# stm32LoRaAccel.net
KiCad netlist of a schematic drawn in Altium Designer
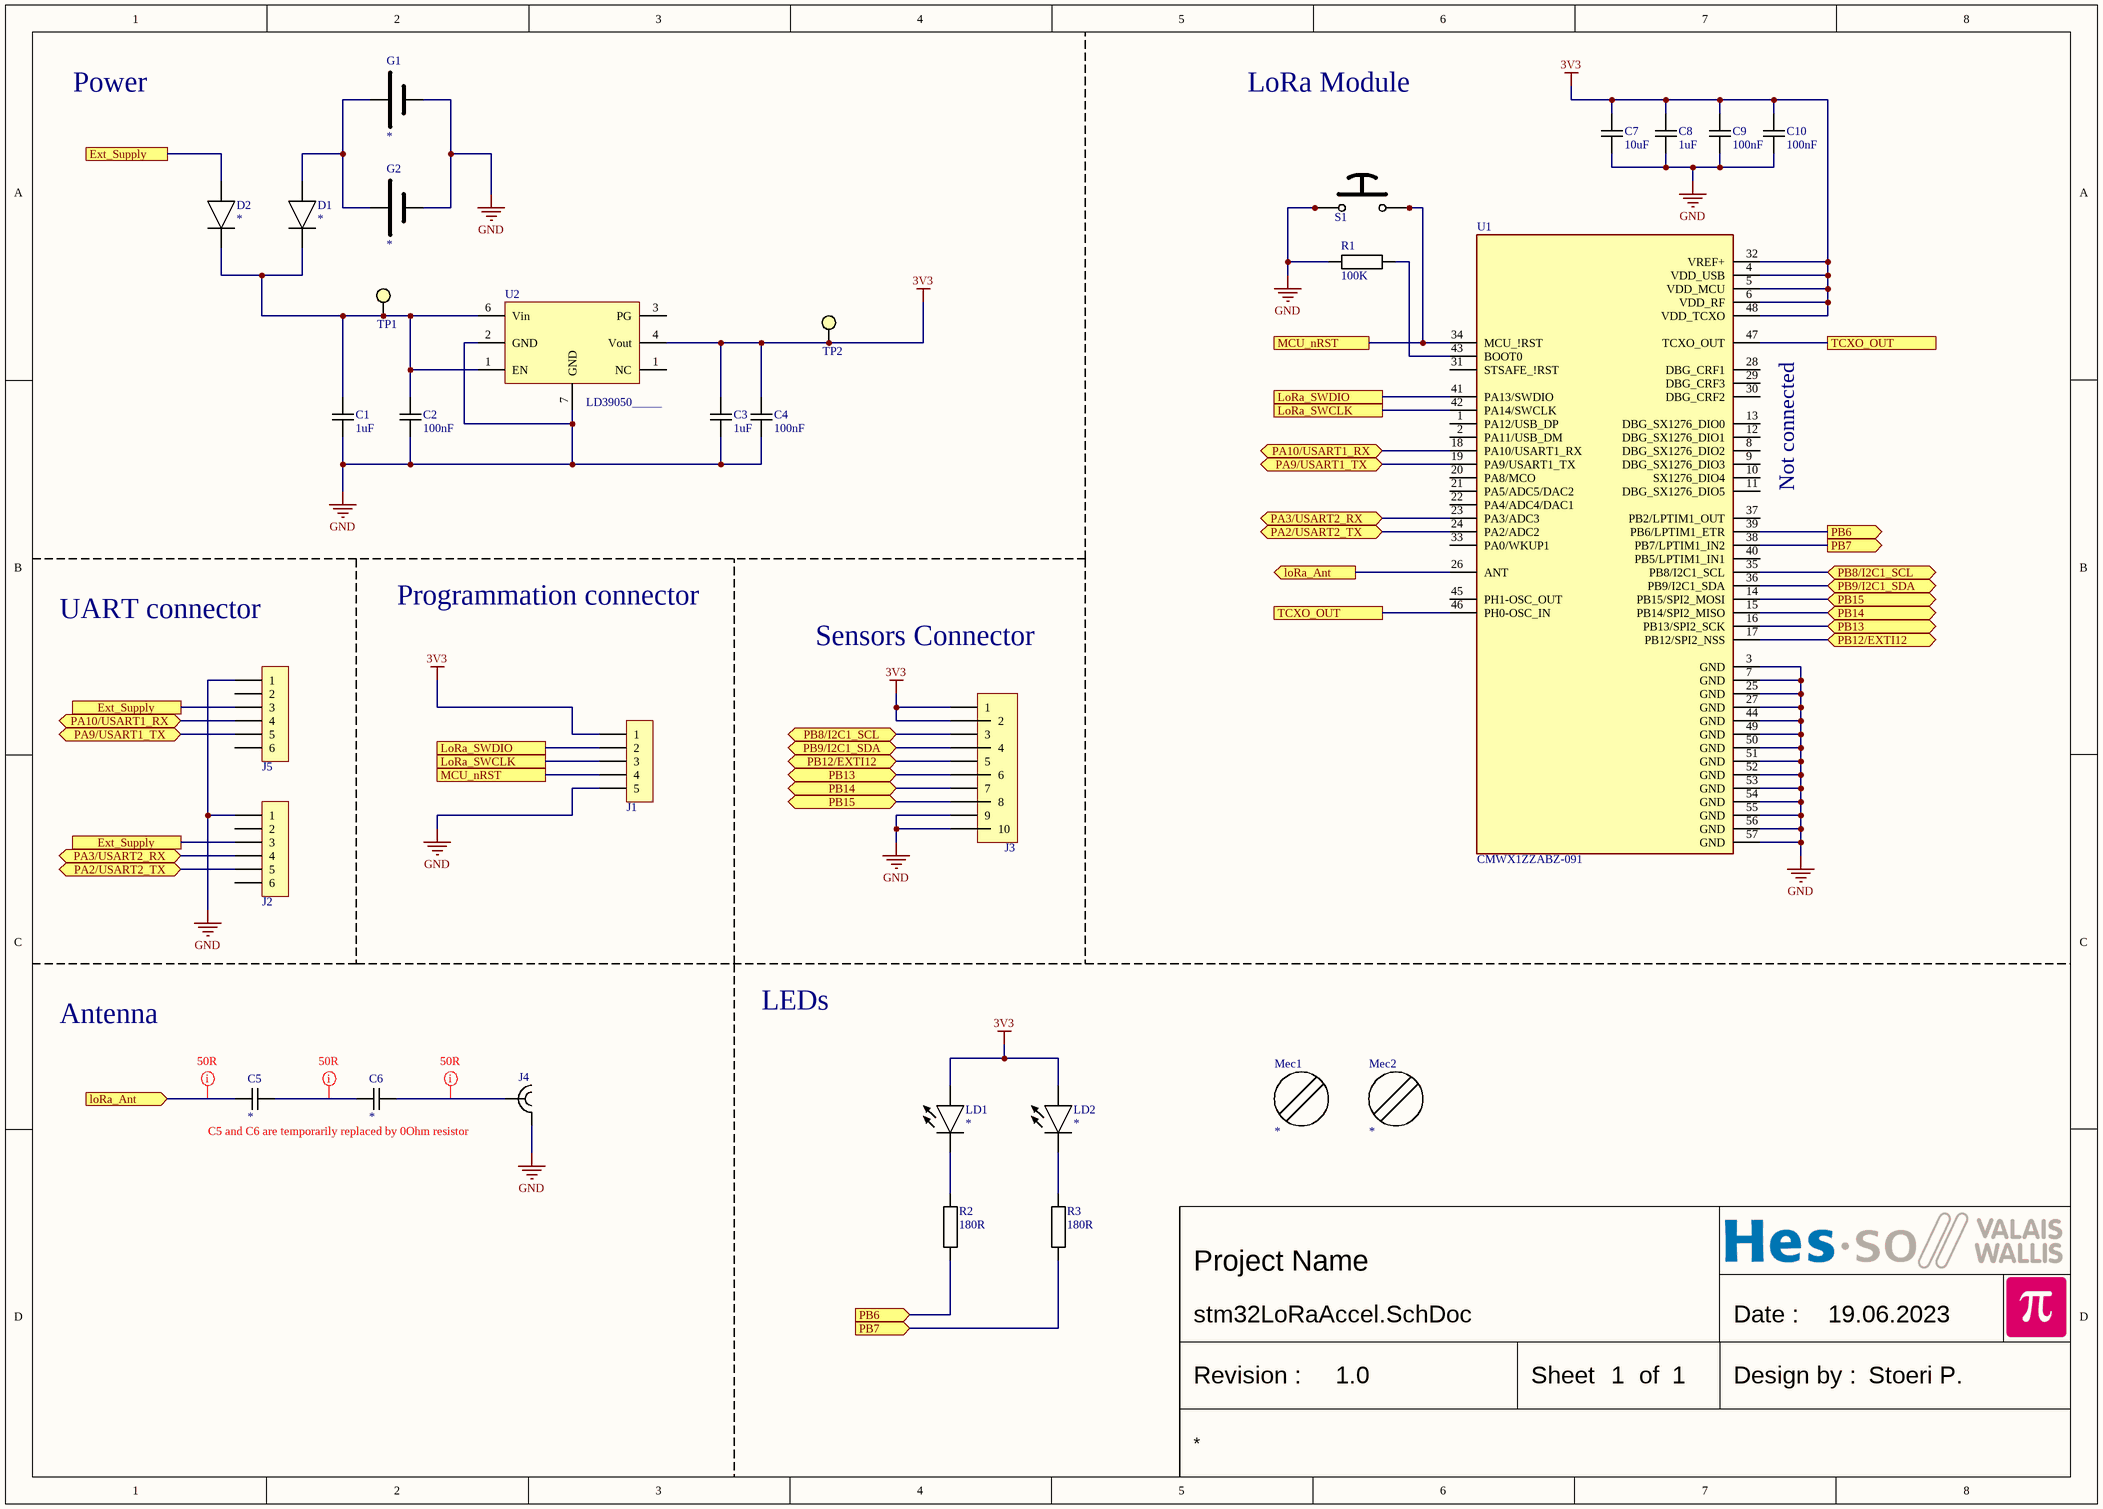
[diagram p0: stm32LoRaAccel.SchDoc]

(export (version "E")
  (design (tool "Eeschema 10.0.6"))
  (components
    (comp (ref "C1")
      (value "1uF")
      (footprint "CAPACITOR 1608 REFLOW")
      (description "Capacitor")
      (libsource (lib "Capacitor") (part "Capacitor"))
    )
    (comp (ref "C2")
      (value "100nF")
      (footprint "CAPACITOR 1608 REFLOW")
      (description "Capacitor")
      (libsource (lib "Capacitor") (part "Capacitor"))
    )
    (comp (ref "C3")
      (value "1uF")
      (footprint "CAPACITOR 1608 REFLOW")
      (description "Capacitor")
      (libsource (lib "Capacitor") (part "Capacitor"))
    )
    (comp (ref "C4")
      (value "100nF")
      (footprint "CAPACITOR 1608 REFLOW")
      (description "Capacitor")
      (libsource (lib "Capacitor") (part "Capacitor"))
    )
    (comp (ref "C5")
      (value "*")
      (footprint "CAPACITOR 1608 REFLOW")
      (description "Capacitor")
      (libsource (lib "Capacitor") (part "Capacitor"))
    )
    (comp (ref "C6")
      (value "*")
      (footprint "CAPACITOR 1608 REFLOW")
      (description "Capacitor")
      (libsource (lib "Capacitor") (part "Capacitor"))
    )
    (comp (ref "C7")
      (value "10uF")
      (footprint "CAPACITOR 1608 REFLOW")
      (description "Capacitor")
      (libsource (lib "Capacitor") (part "Capacitor"))
    )
    (comp (ref "C8")
      (value "1uF")
      (footprint "CAPACITOR 1608 REFLOW")
      (description "Capacitor")
      (libsource (lib "Capacitor") (part "Capacitor"))
    )
    (comp (ref "C9")
      (value "100nF")
      (footprint "CAPACITOR 1608 REFLOW")
      (description "Capacitor")
      (libsource (lib "Capacitor") (part "Capacitor"))
    )
    (comp (ref "C10")
      (value "100nF")
      (footprint "CAPACITOR 1608 REFLOW")
      (description "Capacitor")
      (libsource (lib "Capacitor") (part "Capacitor"))
    )
    (comp (ref "D1")
      (value "*")
      (footprint "DIODE DO-214AC (SMA)")
      (description "Diode generic 2 leads")
      (libsource (lib "Diode") (part "DIODE"))
    )
    (comp (ref "D2")
      (value "*")
      (footprint "DIODE DO-214AC (SMA)")
      (description "Diode generic 2 leads")
      (libsource (lib "Diode") (part "DIODE"))
    )
    (comp (ref "G1")
      (value "*")
      (footprint "Battery Holder Keystone 18650 TH 1131")
      (description "Battery Generic")
      (libsource (lib "Battery") (part "Battery"))
    )
    (comp (ref "G2")
      (value "*")
      (footprint "Battery Holder Keystone 18650 TH 1131")
      (description "Battery Generic")
      (libsource (lib "Battery") (part "Battery"))
    )
    (comp (ref "J1")
      (value "*")
      (footprint "PinHeader1x5 P2.54")
      (description "Plug connector")
      (libsource (lib "PinHeader") (part "PinHeader1x5"))
    )
    (comp (ref "J2")
      (value "*")
      (footprint "PinHeader1x6 P2.54")
      (description "Plug connector")
      (libsource (lib "PinHeader") (part "PinHeader1x6"))
    )
    (comp (ref "J3")
      (value "*")
      (footprint "PinHeader2x5 P1.27 SMD H5.9")
      (description "Plug connector")
      (libsource (lib "PinHeader") (part "PinHeader2x5"))
    )
    (comp (ref "J4")
      (value "CONSMA001-G")
      (footprint "SMA EDGE SAMTEC SMA-J-P-H-ST-EM1")
      (description "SMA EDGE SAMTEC SMA-J-P-H-ST-EM1")
      (libsource (lib "Connector") (part "SMA EDGE SAMTEC SMA-J-P-H-ST-EM1"))
    )
    (comp (ref "J5")
      (value "*")
      (footprint "PinHeader1x6 P2.54")
      (description "Plug connector")
      (libsource (lib "PinHeader") (part "PinHeader1x6"))
    )
    (comp (ref "LD1")
      (value "*")
      (footprint "LED 1608 REFLOW")
      (description "LED generic")
      (libsource (lib "Diode") (part "LED"))
    )
    (comp (ref "LD2")
      (value "*")
      (footprint "LED 1608 REFLOW")
      (description "LED generic")
      (libsource (lib "Diode") (part "LED"))
    )
    (comp (ref "Mec1")
      (value "*")
      (footprint "Screw M3X5 Unconnected")
      (description "Screw Unconnected BN330")
      (libsource (lib "Mechanic") (part "Screw Unconnected"))
    )
    (comp (ref "Mec2")
      (value "*")
      (footprint "Screw M3X5 Unconnected")
      (description "Screw Unconnected BN330")
      (libsource (lib "Mechanic") (part "Screw Unconnected"))
    )
    (comp (ref "R1")
      (value "100K")
      (footprint "RESISTOR 1608 REFLOW")
      (description "Resistor")
      (libsource (lib "Resistor") (part "Resistor"))
    )
    (comp (ref "R2")
      (value "180R")
      (footprint "RESISTOR 1608 REFLOW")
      (description "Resistor")
      (libsource (lib "Resistor") (part "Resistor"))
    )
    (comp (ref "R3")
      (value "180R")
      (footprint "RESISTOR 1608 REFLOW")
      (description "Resistor")
      (libsource (lib "Resistor") (part "Resistor"))
    )
    (comp (ref "S1")
      (value "*")
      (footprint "Push Button C6.0x6.0 TE FSM-2J-SMA")
      (description "Push Button, 4 pins, 2 poles parrallèle")
      (libsource (lib "Button") (part "Push Button 4Pins"))
    )
    (comp (ref "TP1")
      (value "*")
      (footprint "Test Point Keystone Compact BLUE")
      (description "Test Point")
      (libsource (lib "Testpoint") (part "Test Point"))
    )
    (comp (ref "TP2")
      (value "*")
      (footprint "Test Point Keystone Compact BLUE")
      (description "Test Point")
      (libsource (lib "Testpoint") (part "Test Point"))
    )
    (comp (ref "U1")
      (value "CMWX1ZZABZ-091")
      (footprint "CMWX1ZZABZ-091")
      (description "General ISM < 1GHz LoRaWan Transceiver Module 868MHz, 915MHz Surface Mount")
      (fields (field (name "MF") "Murata Electronics"))
      (libsource (lib "WirelessDevice") (part "CMWX1ZZABZ-091"))
    )
    (comp (ref "U2")
      (value "LD39050_____")
      (footprint "DFN6 P0.95 T1.75X2.50 C3.0X3.0 H1.0")
      (description "500 mA low quiescent current and low noise voltage regulator")
      (fields (field (name "MANUFACTURER") "ST"))
      (libsource (lib "Regulator") (part "LD39050_____"))
    )
  )
  (nets
    (net (code "1") (name "/Ext_Supply") (class "Default")
      (node (ref "D2") (pin "2") (pinfunction "A_2") (pintype "passive"))
      (node (ref "J2") (pin "3") (pinfunction "3_3") (pintype "passive"))
      (node (ref "J5") (pin "3") (pinfunction "3_3") (pintype "passive"))
    )
    (net (code "2") (name "/LoRa_SWCLK") (class "Default")
      (node (ref "J1") (pin "3") (pinfunction "3_3") (pintype "passive"))
      (node (ref "U1") (pin "42") (pinfunction "PA14/SWCLK_42") (pintype "passive"))
    )
    (net (code "3") (name "/LoRa_SWDIO") (class "Default")
      (node (ref "J1") (pin "2") (pinfunction "2_2") (pintype "passive"))
      (node (ref "U1") (pin "41") (pinfunction "PA13/SWDIO_41") (pintype "passive"))
    )
    (net (code "4") (name "/MCU_nRST") (class "Default")
      (node (ref "J1") (pin "4") (pinfunction "4_4") (pintype "passive"))
      (node (ref "S1") (pin "3") (pinfunction "3_3") (pintype "passive"))
      (node (ref "S1") (pin "4") (pinfunction "4_4") (pintype "passive"))
      (node (ref "U1") (pin "34") (pinfunction "MCU_!RST_34") (pintype "passive"))
    )
    (net (code "5") (name "/PA2{slash}USART2_TX") (class "Default")
      (node (ref "J2") (pin "5") (pinfunction "5_5") (pintype "passive"))
      (node (ref "U1") (pin "24") (pinfunction "PA2/ADC2_24") (pintype "passive"))
    )
    (net (code "6") (name "/PA3{slash}USART2_RX") (class "Default")
      (node (ref "J2") (pin "4") (pinfunction "4_4") (pintype "passive"))
      (node (ref "U1") (pin "23") (pinfunction "PA3/ADC3_23") (pintype "passive"))
    )
    (net (code "7") (name "/PA9{slash}USART1_TX") (class "Default")
      (node (ref "J5") (pin "5") (pinfunction "5_5") (pintype "passive"))
      (node (ref "U1") (pin "19") (pinfunction "PA9/USART1_TX_19") (pintype "passive"))
    )
    (net (code "8") (name "/PA10{slash}USART1_RX") (class "Default")
      (node (ref "J5") (pin "4") (pinfunction "4_4") (pintype "passive"))
      (node (ref "U1") (pin "18") (pinfunction "PA10/USART1_RX_18") (pintype "passive"))
    )
    (net (code "9") (name "/PB6") (class "Default")
      (node (ref "R2") (pin "2") (pinfunction "2_2") (pintype "passive"))
      (node (ref "U1") (pin "39") (pinfunction "PB6/LPTIM1_ETR_39") (pintype "passive"))
    )
    (net (code "10") (name "/PB7") (class "Default")
      (node (ref "R3") (pin "2") (pinfunction "2_2") (pintype "passive"))
      (node (ref "U1") (pin "38") (pinfunction "PB7/LPTIM1_IN2_38") (pintype "passive"))
    )
    (net (code "11") (name "/PB8{slash}I2C1_SCL") (class "Default")
      (node (ref "J3") (pin "3") (pinfunction "3_3") (pintype "passive"))
      (node (ref "U1") (pin "35") (pinfunction "PB8/I2C1_SCL_35") (pintype "passive"))
    )
    (net (code "12") (name "/PB9{slash}I2C1_SDA") (class "Default")
      (node (ref "J3") (pin "4") (pinfunction "4_4") (pintype "passive"))
      (node (ref "U1") (pin "36") (pinfunction "PB9/I2C1_SDA_36") (pintype "passive"))
    )
    (net (code "13") (name "/PB12{slash}EXTI12") (class "Default")
      (node (ref "J3") (pin "5") (pinfunction "5_5") (pintype "passive"))
      (node (ref "U1") (pin "17") (pinfunction "PB12/SPI2_NSS_17") (pintype "passive"))
    )
    (net (code "14") (name "/PB13") (class "Default")
      (node (ref "J3") (pin "6") (pinfunction "6_6") (pintype "passive"))
      (node (ref "U1") (pin "16") (pinfunction "PB13/SPI2_SCK_16") (pintype "passive"))
    )
    (net (code "15") (name "/PB14") (class "Default")
      (node (ref "J3") (pin "7") (pinfunction "7_7") (pintype "passive"))
      (node (ref "U1") (pin "15") (pinfunction "PB14/SPI2_MISO_15") (pintype "passive"))
    )
    (net (code "16") (name "/PB15") (class "Default")
      (node (ref "J3") (pin "8") (pinfunction "8_8") (pintype "passive"))
      (node (ref "U1") (pin "14") (pinfunction "PB15/SPI2_MOSI_14") (pintype "passive"))
    )
    (net (code "17") (name "/TCXO_OUT") (class "Default")
      (node (ref "U1") (pin "46") (pinfunction "PH0-OSC_IN_46") (pintype "passive"))
      (node (ref "U1") (pin "47") (pinfunction "TCXO_OUT_47") (pintype "passive"))
    )
    (net (code "18") (name "/loRa_Ant") (class "Default")
      (node (ref "C5") (pin "2") (pinfunction "2_2") (pintype "passive"))
      (node (ref "U1") (pin "26") (pinfunction "ANT_26") (pintype "passive"))
    )
    (net (code "19") (name "3V3") (class "Default")
      (node (ref "C10") (pin "1") (pinfunction "1_1") (pintype "passive"))
      (node (ref "C3") (pin "1") (pinfunction "1_1") (pintype "passive"))
      (node (ref "C4") (pin "1") (pinfunction "1_1") (pintype "passive"))
      (node (ref "C7") (pin "1") (pinfunction "1_1") (pintype "passive"))
      (node (ref "C8") (pin "1") (pinfunction "1_1") (pintype "passive"))
      (node (ref "C9") (pin "1") (pinfunction "1_1") (pintype "passive"))
      (node (ref "J1") (pin "1") (pinfunction "1_1") (pintype "passive"))
      (node (ref "J3") (pin "1") (pinfunction "1_1") (pintype "passive"))
      (node (ref "J3") (pin "2") (pinfunction "2_2") (pintype "passive"))
      (node (ref "LD1") (pin "2") (pinfunction "A_2") (pintype "passive"))
      (node (ref "LD2") (pin "2") (pinfunction "A_2") (pintype "passive"))
      (node (ref "TP2") (pin "1") (pinfunction "1_1") (pintype "passive"))
      (node (ref "U1") (pin "32") (pinfunction "VREF+_32") (pintype "passive"))
      (node (ref "U1") (pin "4") (pinfunction "VDD_USB_4") (pintype "passive"))
      (node (ref "U1") (pin "48") (pinfunction "VDD_TCXO_48") (pintype "passive"))
      (node (ref "U1") (pin "5") (pinfunction "VDD_MCU_5") (pintype "passive"))
      (node (ref "U1") (pin "6") (pinfunction "VDD_RF_6") (pintype "passive"))
      (node (ref "U2") (pin "4") (pinfunction "Vout_4") (pintype "passive"))
    )
    (net (code "20") (name "GND") (class "Default")
      (node (ref "C1") (pin "2") (pinfunction "2_2") (pintype "passive"))
      (node (ref "C10") (pin "2") (pinfunction "2_2") (pintype "passive"))
      (node (ref "C2") (pin "2") (pinfunction "2_2") (pintype "passive"))
      (node (ref "C3") (pin "2") (pinfunction "2_2") (pintype "passive"))
      (node (ref "C4") (pin "2") (pinfunction "2_2") (pintype "passive"))
      (node (ref "C7") (pin "2") (pinfunction "2_2") (pintype "passive"))
      (node (ref "C8") (pin "2") (pinfunction "2_2") (pintype "passive"))
      (node (ref "C9") (pin "2") (pinfunction "2_2") (pintype "passive"))
      (node (ref "G1") (pin "2") (pinfunction "—_2") (pintype "passive"))
      (node (ref "G2") (pin "2") (pinfunction "—_2") (pintype "passive"))
      (node (ref "J1") (pin "5") (pinfunction "5_5") (pintype "passive"))
      (node (ref "J2") (pin "1") (pinfunction "1_1") (pintype "passive"))
      (node (ref "J3") (pin "10") (pinfunction "10_10") (pintype "passive"))
      (node (ref "J3") (pin "9") (pinfunction "9_9") (pintype "passive"))
      (node (ref "J4") (pin "2") (pinfunction "2_2") (pintype "passive"))
      (node (ref "J5") (pin "1") (pinfunction "1_1") (pintype "passive"))
      (node (ref "R1") (pin "2") (pinfunction "2_2") (pintype "passive"))
      (node (ref "S1") (pin "1") (pinfunction "1_1") (pintype "passive"))
      (node (ref "S1") (pin "2") (pinfunction "2_2") (pintype "passive"))
      (node (ref "U1") (pin "25") (pinfunction "GND_25") (pintype "passive"))
      (node (ref "U1") (pin "27") (pinfunction "GND_27") (pintype "passive"))
      (node (ref "U1") (pin "3") (pinfunction "GND_3") (pintype "passive"))
      (node (ref "U1") (pin "44") (pinfunction "GND_44") (pintype "passive"))
      (node (ref "U1") (pin "49") (pinfunction "GND_49") (pintype "passive"))
      (node (ref "U1") (pin "50") (pinfunction "GND_50") (pintype "passive"))
      (node (ref "U1") (pin "51") (pinfunction "GND_51") (pintype "passive"))
      (node (ref "U1") (pin "52") (pinfunction "GND_52") (pintype "passive"))
      (node (ref "U1") (pin "53") (pinfunction "GND_53") (pintype "passive"))
      (node (ref "U1") (pin "54") (pinfunction "GND_54") (pintype "passive"))
      (node (ref "U1") (pin "55") (pinfunction "GND_55") (pintype "passive"))
      (node (ref "U1") (pin "56") (pinfunction "GND_56") (pintype "passive"))
      (node (ref "U1") (pin "57") (pinfunction "GND_57") (pintype "passive"))
      (node (ref "U1") (pin "7") (pinfunction "GND_7") (pintype "passive"))
      (node (ref "U2") (pin "2") (pinfunction "GND_2") (pintype "passive"))
      (node (ref "U2") (pin "7") (pinfunction "GND_7") (pintype "passive"))
    )
    (net (code "21") (name "Net-(C5-Pad1)") (class "Default")
      (node (ref "C5") (pin "1") (pinfunction "1_1") (pintype "passive"))
      (node (ref "C6") (pin "2") (pinfunction "2_2") (pintype "passive"))
    )
    (net (code "22") (name "Net-(C6-Pad1)") (class "Default")
      (node (ref "C6") (pin "1") (pinfunction "1_1") (pintype "passive"))
      (node (ref "J4") (pin "1") (pinfunction "1_1") (pintype "passive"))
    )
    (net (code "23") (name "Net-(D1-A)") (class "Default")
      (node (ref "D1") (pin "2") (pinfunction "A_2") (pintype "passive"))
      (node (ref "G1") (pin "1") (pinfunction "+_1") (pintype "passive"))
      (node (ref "G2") (pin "1") (pinfunction "+_1") (pintype "passive"))
    )
    (net (code "24") (name "Net-(D1-C)") (class "Default")
      (node (ref "C1") (pin "1") (pinfunction "1_1") (pintype "passive"))
      (node (ref "C2") (pin "1") (pinfunction "1_1") (pintype "passive"))
      (node (ref "D1") (pin "1") (pinfunction "C_1") (pintype "passive"))
      (node (ref "D2") (pin "1") (pinfunction "C_1") (pintype "passive"))
      (node (ref "TP1") (pin "1") (pinfunction "1_1") (pintype "passive"))
      (node (ref "U2") (pin "1") (pinfunction "EN_1") (pintype "passive"))
      (node (ref "U2") (pin "6") (pinfunction "Vin_6") (pintype "passive"))
    )
    (net (code "25") (name "Net-(LD1-C)") (class "Default")
      (node (ref "LD1") (pin "1") (pinfunction "C_1") (pintype "passive"))
      (node (ref "R2") (pin "1") (pinfunction "1_1") (pintype "passive"))
    )
    (net (code "26") (name "Net-(LD2-C)") (class "Default")
      (node (ref "LD2") (pin "1") (pinfunction "C_1") (pintype "passive"))
      (node (ref "R3") (pin "1") (pinfunction "1_1") (pintype "passive"))
    )
    (net (code "27") (name "Net-(U1-BOOT0)") (class "Default")
      (node (ref "R1") (pin "1") (pinfunction "1_1") (pintype "passive"))
      (node (ref "U1") (pin "43") (pinfunction "BOOT0_43") (pintype "passive"))
    )
    (net (code "28") (name "unconnected-(J2-Pad2)") (class "Default")
      (node (ref "J2") (pin "2") (pinfunction "2_2") (pintype "passive"))
    )
    (net (code "29") (name "unconnected-(J2-Pad6)") (class "Default")
      (node (ref "J2") (pin "6") (pinfunction "6_6") (pintype "passive"))
    )
    (net (code "30") (name "unconnected-(J5-Pad2)") (class "Default")
      (node (ref "J5") (pin "2") (pinfunction "2_2") (pintype "passive"))
    )
    (net (code "31") (name "unconnected-(J5-Pad6)") (class "Default")
      (node (ref "J5") (pin "6") (pinfunction "6_6") (pintype "passive"))
    )
    (net (code "32") (name "unconnected-(U1-DBG_CRF1-Pad28)") (class "Default")
      (node (ref "U1") (pin "28") (pinfunction "DBG_CRF1_28") (pintype "passive"))
    )
    (net (code "33") (name "unconnected-(U1-DBG_CRF2-Pad30)") (class "Default")
      (node (ref "U1") (pin "30") (pinfunction "DBG_CRF2_30") (pintype "passive"))
    )
    (net (code "34") (name "unconnected-(U1-DBG_CRF3-Pad29)") (class "Default")
      (node (ref "U1") (pin "29") (pinfunction "DBG_CRF3_29") (pintype "passive"))
    )
    (net (code "35") (name "unconnected-(U1-DBG_SX1276_DIO0-Pad13)") (class "Default")
      (node (ref "U1") (pin "13") (pinfunction "DBG_SX1276_DIO0_13") (pintype "passive"))
    )
    (net (code "36") (name "unconnected-(U1-DBG_SX1276_DIO1-Pad12)") (class "Default")
      (node (ref "U1") (pin "12") (pinfunction "DBG_SX1276_DIO1_12") (pintype "passive"))
    )
    (net (code "37") (name "unconnected-(U1-DBG_SX1276_DIO2-Pad8)") (class "Default")
      (node (ref "U1") (pin "8") (pinfunction "DBG_SX1276_DIO2_8") (pintype "passive"))
    )
    (net (code "38") (name "unconnected-(U1-DBG_SX1276_DIO3-Pad9)") (class "Default")
      (node (ref "U1") (pin "9") (pinfunction "DBG_SX1276_DIO3_9") (pintype "passive"))
    )
    (net (code "39") (name "unconnected-(U1-DBG_SX1276_DIO5-Pad11)") (class "Default")
      (node (ref "U1") (pin "11") (pinfunction "DBG_SX1276_DIO5_11") (pintype "passive"))
    )
    (net (code "40") (name "unconnected-(U1-PA0{slash}WKUP1-Pad33)") (class "Default")
      (node (ref "U1") (pin "33") (pinfunction "PA0/WKUP1_33") (pintype "passive"))
    )
    (net (code "41") (name "unconnected-(U1-PA4{slash}ADC4{slash}DAC1-Pad22)") (class "Default")
      (node (ref "U1") (pin "22") (pinfunction "PA4/ADC4/DAC1_22") (pintype "passive"))
    )
    (net (code "42") (name "unconnected-(U1-PA5{slash}ADC5{slash}DAC2-Pad21)") (class "Default")
      (node (ref "U1") (pin "21") (pinfunction "PA5/ADC5/DAC2_21") (pintype "passive"))
    )
    (net (code "43") (name "unconnected-(U1-PA8{slash}MCO-Pad20)") (class "Default")
      (node (ref "U1") (pin "20") (pinfunction "PA8/MCO_20") (pintype "passive"))
    )
    (net (code "44") (name "unconnected-(U1-PA11{slash}USB_DM-Pad2)") (class "Default")
      (node (ref "U1") (pin "2") (pinfunction "PA11/USB_DM_2") (pintype "passive"))
    )
    (net (code "45") (name "unconnected-(U1-PA12{slash}USB_DP-Pad1)") (class "Default")
      (node (ref "U1") (pin "1") (pinfunction "PA12/USB_DP_1") (pintype "passive"))
    )
    (net (code "46") (name "unconnected-(U1-PB2{slash}LPTIM1_OUT-Pad37)") (class "Default")
      (node (ref "U1") (pin "37") (pinfunction "PB2/LPTIM1_OUT_37") (pintype "passive"))
    )
    (net (code "47") (name "unconnected-(U1-PB5{slash}LPTIM1_IN1-Pad40)") (class "Default")
      (node (ref "U1") (pin "40") (pinfunction "PB5/LPTIM1_IN1_40") (pintype "passive"))
    )
    (net (code "48") (name "unconnected-(U1-PH1-OSC_OUT-Pad45)") (class "Default")
      (node (ref "U1") (pin "45") (pinfunction "PH1-OSC_OUT_45") (pintype "passive"))
    )
    (net (code "49") (name "unconnected-(U1-STSAFE_!RST-Pad31)") (class "Default")
      (node (ref "U1") (pin "31") (pinfunction "STSAFE_!RST_31") (pintype "passive"))
    )
    (net (code "50") (name "unconnected-(U1-SX1276_DIO4-Pad10)") (class "Default")
      (node (ref "U1") (pin "10") (pinfunction "SX1276_DIO4_10") (pintype "passive"))
    )
    (net (code "51") (name "unconnected-(U2-NC-Pad1)") (class "Default")
      (node (ref "U2") (pin "1") (pinfunction "NC_1") (pintype "passive"))
    )
    (net (code "52") (name "unconnected-(U2-PG-Pad3)") (class "Default")
      (node (ref "U2") (pin "3") (pinfunction "PG_3") (pintype "passive"))
    )
  )
)
